# Remote_Circuit_Sch.net
KiCad netlist of a schematic drawn in Altium Designer
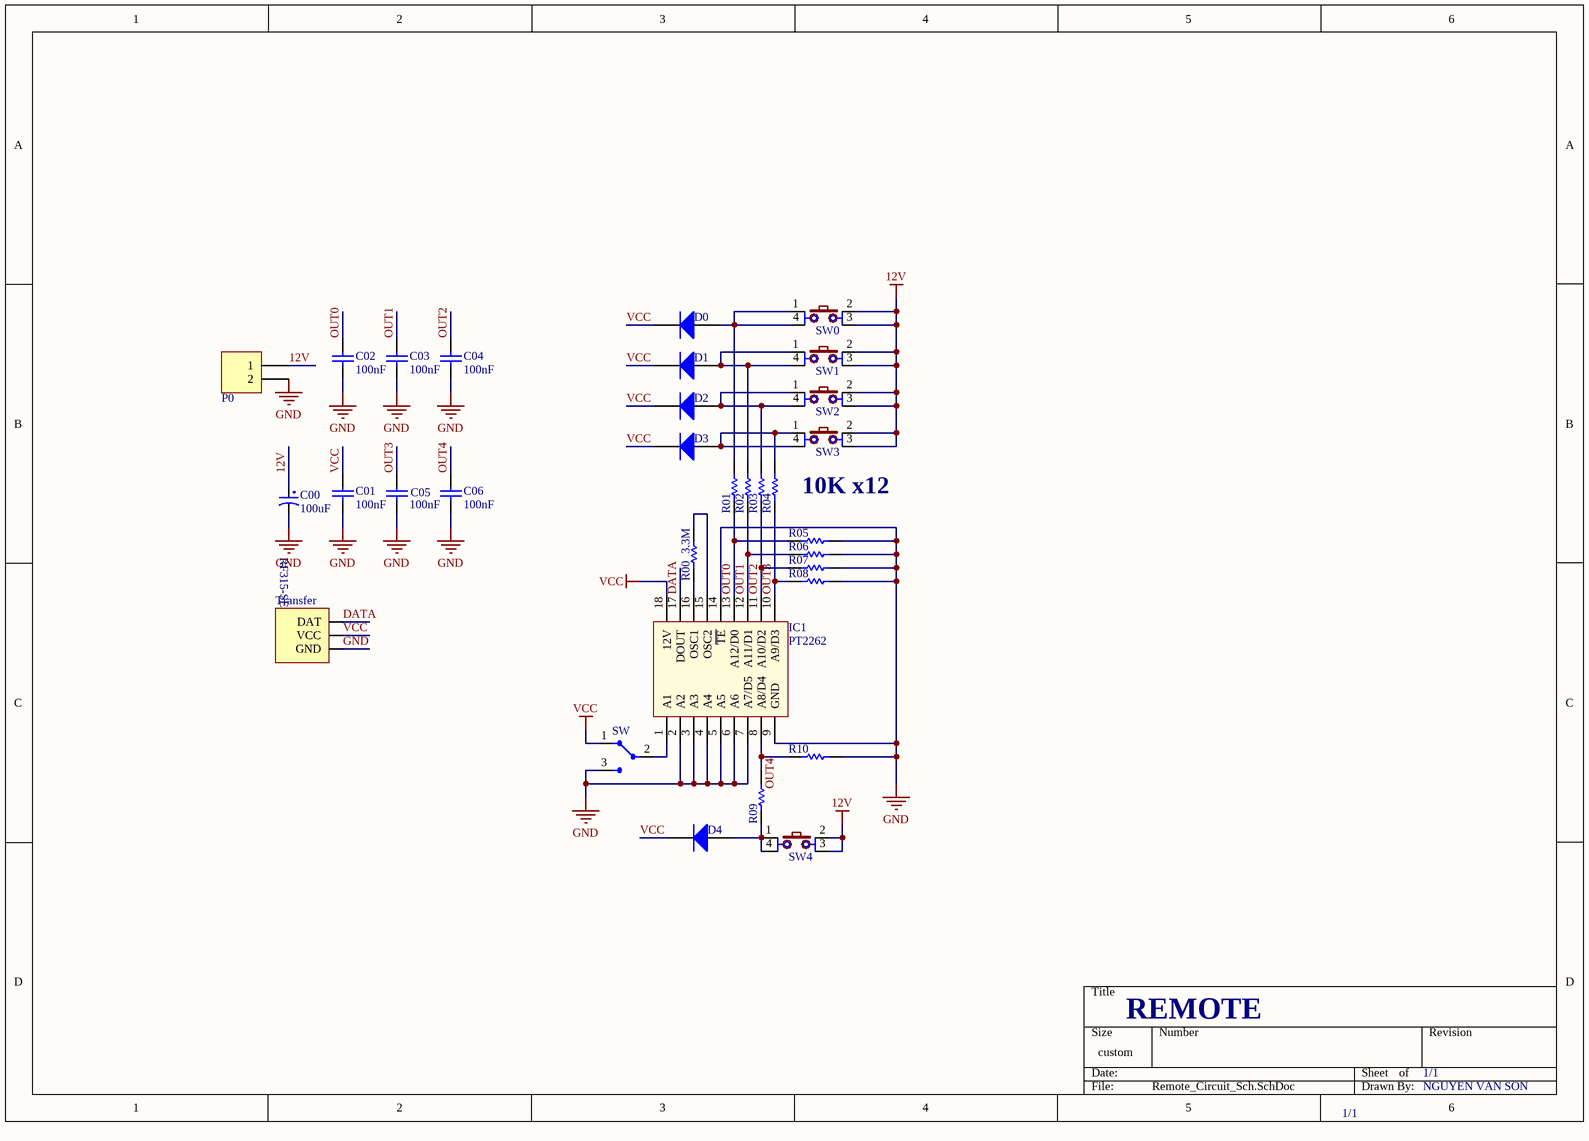
[diagram p0: Remote_Circuit_Sch.SchDoc]

(export (version "E")
  (design (tool "Eeschema 10.0.6"))
  (components
    (comp (ref "C00")
      (value "100uF")
      (footprint "tu tantalum smd7343")
      (description "Dán")
      (libsource (lib "Altium_Lib_by_KhueNguyenCreator") (part "Tu tantalum 100uF 50V SMD7343"))
    )
    (comp (ref "C01")
      (value "100nF")
      (footprint "CAP-SM-0603")
      (description "Capacitor")
      (fields (field (name "Comment") "Cap Non-Pol SMD"))
      (libsource (lib "PIF_Library") (part "Cap Non-Pol SMD"))
    )
    (comp (ref "C02")
      (value "100nF")
      (footprint "CAP-SM-0603")
      (description "Capacitor")
      (fields (field (name "Comment") "Cap Non-Pol SMD"))
      (libsource (lib "PIF_Library") (part "Cap Non-Pol SMD"))
    )
    (comp (ref "C03")
      (value "100nF")
      (footprint "CAP-SM-0603")
      (description "Capacitor")
      (fields (field (name "Comment") "Cap Non-Pol SMD"))
      (libsource (lib "PIF_Library") (part "Cap Non-Pol SMD"))
    )
    (comp (ref "C04")
      (value "100nF")
      (footprint "CAP-SM-0603")
      (description "Capacitor")
      (fields (field (name "Comment") "Cap Non-Pol SMD"))
      (libsource (lib "PIF_Library") (part "Cap Non-Pol SMD"))
    )
    (comp (ref "C05")
      (value "100nF")
      (footprint "CAP-SM-0603")
      (description "Capacitor")
      (fields (field (name "Comment") "Cap Non-Pol SMD"))
      (libsource (lib "PIF_Library") (part "Cap Non-Pol SMD"))
    )
    (comp (ref "C06")
      (value "100nF")
      (footprint "CAP-SM-0603")
      (description "Capacitor")
      (fields (field (name "Comment") "Cap Non-Pol SMD"))
      (libsource (lib "PIF_Library") (part "Cap Non-Pol SMD"))
    )
    (comp (ref "D0")
      (value "M7")
      (footprint "DIODE SMA")
      (description "Dán")
      (libsource (lib "Altium_Lib_by_KhueNguyenCreator") (part "Diode M7 ( 4007 )"))
    )
    (comp (ref "D1")
      (value "M7")
      (footprint "DIODE SMA")
      (description "Dán")
      (libsource (lib "Altium_Lib_by_KhueNguyenCreator") (part "Diode M7 ( 4007 )"))
    )
    (comp (ref "D2")
      (value "M7")
      (footprint "DIODE SMA")
      (description "Dán")
      (libsource (lib "Altium_Lib_by_KhueNguyenCreator") (part "Diode M7 ( 4007 )"))
    )
    (comp (ref "D3")
      (value "M7")
      (footprint "DIODE SMA")
      (description "Dán")
      (libsource (lib "Altium_Lib_by_KhueNguyenCreator") (part "Diode M7 ( 4007 )"))
    )
    (comp (ref "D4")
      (value "M7")
      (footprint "DIODE SMA")
      (description "Dán")
      (libsource (lib "Altium_Lib_by_KhueNguyenCreator") (part "Diode M7 ( 4007 )"))
    )
    (comp (ref "IC1")
      (value "PT2262")
      (footprint "DIP18")
      (description "Remote Control Encoder")
      (libsource (lib "TechMT.VN_Lib_Project v2") (part "PT2262"))
    )
    (comp (ref "P0")
      (value "Domino 2")
      (footprint "DOMINO SMALL 2")
      (description "Domino, 2-Pin")
      (fields (field (name "PUBLISHER") "Altium Limited"))
      (libsource (lib "PIF_Library") (part "Domino 2"))
    )
    (comp (ref "R00")
      (value "3.3M")
      (footprint "RES-SM-0603")
      (description "Resistor")
      (fields (field (name "Comment") "RESISTOR SMD"))
      (libsource (lib "PIF_Library") (part "RESISTOR SMD"))
    )
    (comp (ref "R01")
      (value "RESISTOR SMD")
      (footprint "RES-SM-0603")
      (description "Resistor")
      (libsource (lib "PIF_Library") (part "RESISTOR SMD"))
    )
    (comp (ref "R02")
      (value "RESISTOR SMD")
      (footprint "RES-SM-0603")
      (description "Resistor")
      (libsource (lib "PIF_Library") (part "RESISTOR SMD"))
    )
    (comp (ref "R03")
      (value "RESISTOR SMD")
      (footprint "RES-SM-0603")
      (description "Resistor")
      (libsource (lib "PIF_Library") (part "RESISTOR SMD"))
    )
    (comp (ref "R04")
      (value "RESISTOR SMD")
      (footprint "RES-SM-0603")
      (description "Resistor")
      (libsource (lib "PIF_Library") (part "RESISTOR SMD"))
    )
    (comp (ref "R05")
      (value "RESISTOR SMD")
      (footprint "RES-SM-0603")
      (description "Resistor")
      (libsource (lib "PIF_Library") (part "RESISTOR SMD"))
    )
    (comp (ref "R06")
      (value "RESISTOR SMD")
      (footprint "RES-SM-0603")
      (description "Resistor")
      (libsource (lib "PIF_Library") (part "RESISTOR SMD"))
    )
    (comp (ref "R07")
      (value "RESISTOR SMD")
      (footprint "RES-SM-0603")
      (description "Resistor")
      (libsource (lib "PIF_Library") (part "RESISTOR SMD"))
    )
    (comp (ref "R08")
      (value "RESISTOR SMD")
      (footprint "RES-SM-0603")
      (description "Resistor")
      (libsource (lib "PIF_Library") (part "RESISTOR SMD"))
    )
    (comp (ref "R09")
      (value "RESISTOR SMD")
      (footprint "RES-SM-0603")
      (description "Resistor")
      (libsource (lib "PIF_Library") (part "RESISTOR SMD"))
    )
    (comp (ref "R10")
      (value "RESISTOR SMD")
      (footprint "RES-SM-0603")
      (description "Resistor")
      (libsource (lib "PIF_Library") (part "RESISTOR SMD"))
    )
    (comp (ref "SW")
      (value "Component_1")
      (footprint "Slide Switch")
      (libsource (lib "Slide_SW") (part "Component_1"))
    )
    (comp (ref "SW0")
      (value "SW")
      (footprint "SW2-DIP")
      (description "Switch button 4 pin")
      (libsource (lib "TechMT.VN_Lib_Project v2") (part "SW4"))
    )
    (comp (ref "SW1")
      (value "SW")
      (footprint "SW2-DIP")
      (description "Switch button 4 pin")
      (libsource (lib "TechMT.VN_Lib_Project v2") (part "SW4"))
    )
    (comp (ref "SW2")
      (value "SW")
      (footprint "SW2-DIP")
      (description "Switch button 4 pin")
      (libsource (lib "TechMT.VN_Lib_Project v2") (part "SW4"))
    )
    (comp (ref "SW3")
      (value "SW")
      (footprint "SW2-DIP")
      (description "Switch button 4 pin")
      (libsource (lib "TechMT.VN_Lib_Project v2") (part "SW4"))
    )
    (comp (ref "SW4")
      (value "SW")
      (footprint "SW2-DIP")
      (description "Switch button 4 pin")
      (libsource (lib "TechMT.VN_Lib_Project v2") (part "SW4"))
    )
    (comp (ref "Transfer")
      (value "RF315-DEND-NOIC")
      (footprint "RF315-SEND-NOIC")
      (fields
        (field (name "MANUFACTURER") "Würth Elektronik eiSos GmbH")
        (field (name "PARTNO") "613004143121")
        (field (name "CREATED BY") "Karrer Zheng")
      )
      (libsource (lib "TechMT.VN_Lib_Project v2") (part "RF315-DEND-NOIC"))
    )
  )
  (nets
    (net (code "1") (name "/DATA") (class "Default")
      (node (ref "IC1") (pin "17") (pinfunction "DOUT_17") (pintype "passive"))
      (node (ref "Transfer") (pin "1") (pinfunction "DAT_1") (pintype "passive"))
    )
    (net (code "2") (name "/OUT0") (class "Default")
      (node (ref "C02") (pin "2") (pinfunction "2_2") (pintype "passive"))
      (node (ref "IC1") (pin "13") (pinfunction "A12/D0_13") (pintype "passive"))
      (node (ref "R01") (pin "1") (pinfunction "1_1") (pintype "passive"))
      (node (ref "R05") (pin "2") (pinfunction "2_2") (pintype "passive"))
    )
    (net (code "3") (name "/OUT1") (class "Default")
      (node (ref "C03") (pin "2") (pinfunction "2_2") (pintype "passive"))
      (node (ref "IC1") (pin "12") (pinfunction "A11/D1_12") (pintype "passive"))
      (node (ref "R02") (pin "1") (pinfunction "1_1") (pintype "passive"))
      (node (ref "R06") (pin "2") (pinfunction "2_2") (pintype "passive"))
    )
    (net (code "4") (name "/OUT2") (class "Default")
      (node (ref "C04") (pin "2") (pinfunction "2_2") (pintype "passive"))
      (node (ref "IC1") (pin "11") (pinfunction "A10/D2_11") (pintype "passive"))
      (node (ref "R03") (pin "1") (pinfunction "1_1") (pintype "passive"))
      (node (ref "R07") (pin "2") (pinfunction "2_2") (pintype "passive"))
    )
    (net (code "5") (name "/OUT3") (class "Default")
      (node (ref "C05") (pin "2") (pinfunction "2_2") (pintype "passive"))
      (node (ref "IC1") (pin "10") (pinfunction "A9/D3_10") (pintype "passive"))
      (node (ref "R04") (pin "1") (pinfunction "1_1") (pintype "passive"))
      (node (ref "R08") (pin "2") (pinfunction "2_2") (pintype "passive"))
    )
    (net (code "6") (name "/OUT4") (class "Default")
      (node (ref "C06") (pin "2") (pinfunction "2_2") (pintype "passive"))
      (node (ref "IC1") (pin "8") (pinfunction "A8/D4_8") (pintype "passive"))
      (node (ref "R09") (pin "1") (pinfunction "1_1") (pintype "passive"))
      (node (ref "R10") (pin "2") (pinfunction "2_2") (pintype "passive"))
    )
    (net (code "7") (name "12V") (class "Default")
      (node (ref "C00") (pin "1") (pinfunction "1_1") (pintype "passive"))
      (node (ref "P0") (pin "1") (pinfunction "1_1") (pintype "passive"))
      (node (ref "SW0") (pin "2") (pinfunction "2_2") (pintype "passive"))
      (node (ref "SW0") (pin "3") (pinfunction "3_3") (pintype "passive"))
      (node (ref "SW1") (pin "2") (pinfunction "2_2") (pintype "passive"))
      (node (ref "SW1") (pin "3") (pinfunction "3_3") (pintype "passive"))
      (node (ref "SW2") (pin "2") (pinfunction "2_2") (pintype "passive"))
      (node (ref "SW2") (pin "3") (pinfunction "3_3") (pintype "passive"))
      (node (ref "SW3") (pin "2") (pinfunction "2_2") (pintype "passive"))
      (node (ref "SW3") (pin "3") (pinfunction "3_3") (pintype "passive"))
      (node (ref "SW4") (pin "2") (pinfunction "2_2") (pintype "passive"))
      (node (ref "SW4") (pin "3") (pinfunction "3_3") (pintype "passive"))
    )
    (net (code "8") (name "GND") (class "Default")
      (node (ref "C00") (pin "2") (pinfunction "2_2") (pintype "passive"))
      (node (ref "C01") (pin "1") (pinfunction "1_1") (pintype "passive"))
      (node (ref "C02") (pin "1") (pinfunction "1_1") (pintype "passive"))
      (node (ref "C03") (pin "1") (pinfunction "1_1") (pintype "passive"))
      (node (ref "C04") (pin "1") (pinfunction "1_1") (pintype "passive"))
      (node (ref "C05") (pin "1") (pinfunction "1_1") (pintype "passive"))
      (node (ref "C06") (pin "1") (pinfunction "1_1") (pintype "passive"))
      (node (ref "IC1") (pin "14") (pinfunction "~{TE}_14") (pintype "passive"))
      (node (ref "IC1") (pin "2") (pinfunction "A2_2") (pintype "passive"))
      (node (ref "IC1") (pin "3") (pinfunction "A3_3") (pintype "passive"))
      (node (ref "IC1") (pin "4") (pinfunction "A4_4") (pintype "passive"))
      (node (ref "IC1") (pin "5") (pinfunction "A5_5") (pintype "passive"))
      (node (ref "IC1") (pin "6") (pinfunction "A6_6") (pintype "passive"))
      (node (ref "IC1") (pin "7") (pinfunction "A7/D5_7") (pintype "passive"))
      (node (ref "IC1") (pin "9") (pinfunction "GND_9") (pintype "passive"))
      (node (ref "P0") (pin "2") (pinfunction "2_2") (pintype "passive"))
      (node (ref "R05") (pin "1") (pinfunction "1_1") (pintype "passive"))
      (node (ref "R06") (pin "1") (pinfunction "1_1") (pintype "passive"))
      (node (ref "R07") (pin "1") (pinfunction "1_1") (pintype "passive"))
      (node (ref "R08") (pin "1") (pinfunction "1_1") (pintype "passive"))
      (node (ref "R10") (pin "1") (pinfunction "1_1") (pintype "passive"))
      (node (ref "SW") (pin "3") (pinfunction "I/O2_3") (pintype "passive"))
      (node (ref "Transfer") (pin "3") (pinfunction "GND_3") (pintype "passive"))
    )
    (net (code "9") (name "Net-(D0-A)") (class "Default")
      (node (ref "D0") (pin "1") (pinfunction "A_1") (pintype "passive"))
      (node (ref "R01") (pin "2") (pinfunction "2_2") (pintype "passive"))
      (node (ref "SW0") (pin "1") (pintype "passive"))
      (node (ref "SW0") (pin "4") (pinfunction "4_4") (pintype "passive"))
    )
    (net (code "10") (name "Net-(D1-A)") (class "Default")
      (node (ref "D1") (pin "1") (pinfunction "A_1") (pintype "passive"))
      (node (ref "R02") (pin "2") (pinfunction "2_2") (pintype "passive"))
      (node (ref "SW1") (pin "1") (pintype "passive"))
      (node (ref "SW1") (pin "4") (pinfunction "4_4") (pintype "passive"))
    )
    (net (code "11") (name "Net-(D2-A)") (class "Default")
      (node (ref "D2") (pin "1") (pinfunction "A_1") (pintype "passive"))
      (node (ref "R03") (pin "2") (pinfunction "2_2") (pintype "passive"))
      (node (ref "SW2") (pin "1") (pintype "passive"))
      (node (ref "SW2") (pin "4") (pinfunction "4_4") (pintype "passive"))
    )
    (net (code "12") (name "Net-(D3-A)") (class "Default")
      (node (ref "D3") (pin "1") (pinfunction "A_1") (pintype "passive"))
      (node (ref "R04") (pin "2") (pinfunction "2_2") (pintype "passive"))
      (node (ref "SW3") (pin "1") (pintype "passive"))
      (node (ref "SW3") (pin "4") (pinfunction "4_4") (pintype "passive"))
    )
    (net (code "13") (name "Net-(D4-A)") (class "Default")
      (node (ref "D4") (pin "1") (pinfunction "A_1") (pintype "passive"))
      (node (ref "R09") (pin "2") (pinfunction "2_2") (pintype "passive"))
      (node (ref "SW4") (pin "1") (pintype "passive"))
      (node (ref "SW4") (pin "4") (pinfunction "4_4") (pintype "passive"))
    )
    (net (code "14") (name "Net-(IC1-A1)") (class "Default")
      (node (ref "IC1") (pin "1") (pinfunction "A1_1") (pintype "passive"))
      (node (ref "SW") (pin "2") (pintype "passive"))
    )
    (net (code "15") (name "Net-(IC1-OSC1)") (class "Default")
      (node (ref "IC1") (pin "16") (pinfunction "OSC1_16") (pintype "passive"))
      (node (ref "R00") (pin "2") (pinfunction "2_2") (pintype "passive"))
    )
    (net (code "16") (name "Net-(IC1-OSC2)") (class "Default")
      (node (ref "IC1") (pin "15") (pinfunction "OSC2_15") (pintype "passive"))
      (node (ref "R00") (pin "1") (pinfunction "1_1") (pintype "passive"))
    )
    (net (code "17") (name "VCC") (class "Default")
      (node (ref "C01") (pin "2") (pinfunction "2_2") (pintype "passive"))
      (node (ref "D0") (pin "2") (pinfunction "K_2") (pintype "passive"))
      (node (ref "D1") (pin "2") (pinfunction "K_2") (pintype "passive"))
      (node (ref "D2") (pin "2") (pinfunction "K_2") (pintype "passive"))
      (node (ref "D3") (pin "2") (pinfunction "K_2") (pintype "passive"))
      (node (ref "D4") (pin "2") (pinfunction "K_2") (pintype "passive"))
      (node (ref "IC1") (pin "18") (pinfunction "12V_18") (pintype "passive"))
      (node (ref "SW") (pin "1") (pintype "passive"))
      (node (ref "Transfer") (pin "2") (pinfunction "VCC_2") (pintype "passive"))
    )
  )
)
